# Voltage_Source.net
KiCad netlist of a schematic drawn in Altium Designer
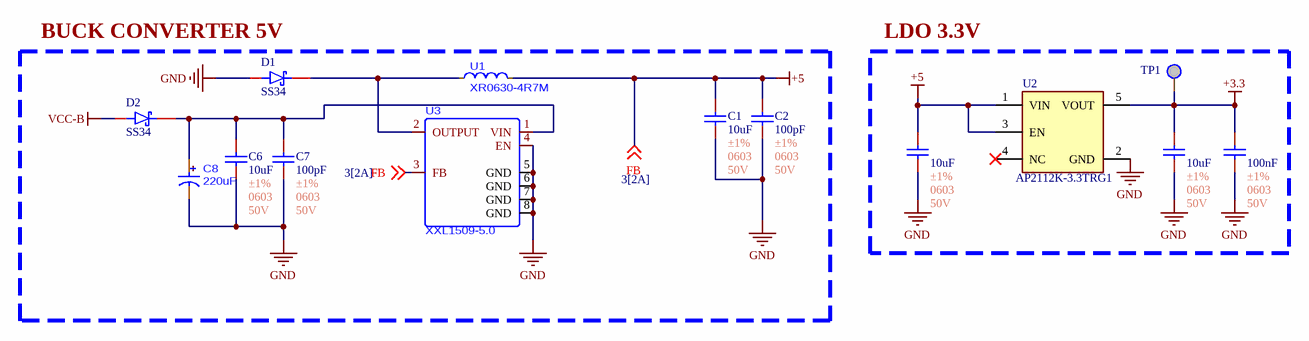
[diagram p0: Voltage Source.SchDoc]

(export (version "E")
  (design (tool "Eeschema 10.0.6"))
  (components
    (comp (ref "C1")
      (value "10uF")
      (footprint "C0603")
      (fields
        (field (name "MANUFACTURER") "YAGEO")
        (field (name "MFR. PART #") "CC0402FRNPO9BN100")
        (field (name "LCSC PART #") "C513681")
        (field (name "TOLERANCE") "±1%")
        (field (name "PACKAGE") "0603")
        (field (name "VOLTAGE RATING") "50V")
      )
      (libsource (lib "Capital") (part "C0603_10uF_±1%"))
    )
    (comp (ref "C2")
      (value "100pF")
      (footprint "C0603")
      (fields
        (field (name "MANUFACTURER") "YAGEO")
        (field (name "MFR. PART #") "CC0402FRNPO9BN100")
        (field (name "LCSC PART #") "C513681")
        (field (name "TOLERANCE") "±1%")
        (field (name "PACKAGE") "0603")
        (field (name "VOLTAGE RATING") "50V")
      )
      (libsource (lib "Capital") (part "C0603_100pF_±1%"))
    )
    (comp (ref "C3")
      (value "10uF")
      (footprint "C0603")
      (description "50V 10pF NP0 ±1% 0402 Multilayer Ceramic Capacitors MLCC - SMD/SMT ROHS")
      (fields
        (field (name "MANUFACTURER") "YAGEO")
        (field (name "MFR. PART #") "CC0402FRNPO9BN100")
        (field (name "TOLERANCE") "±1%")
        (field (name "PACKAGE") "0603")
        (field (name "VOLTAGE RATING") "50V")
      )
      (libsource (lib "") (part "C0603_10uF_±1%_1"))
    )
    (comp (ref "C4")
      (value "10uF")
      (footprint "C0603")
      (description "50V 10pF NP0 ±1% 0402 Multilayer Ceramic Capacitors MLCC - SMD/SMT ROHS")
      (fields
        (field (name "MANUFACTURER") "YAGEO")
        (field (name "MFR. PART #") "CC0402FRNPO9BN100")
        (field (name "TOLERANCE") "±1%")
        (field (name "PACKAGE") "0603")
        (field (name "VOLTAGE RATING") "50V")
      )
      (libsource (lib "") (part "C0603_10uF_±1%_1"))
    )
    (comp (ref "C5")
      (value "100nF")
      (footprint "C0603")
      (description "50V 10pF NP0 ±1% 0402 Multilayer Ceramic Capacitors MLCC - SMD/SMT ROHS")
      (fields
        (field (name "MANUFACTURER") "YAGEO")
        (field (name "MFR. PART #") "CC0402FRNPO9BN100")
        (field (name "TOLERANCE") "±1%")
        (field (name "PACKAGE") "0603")
        (field (name "VOLTAGE RATING") "50V")
      )
      (libsource (lib "Capital") (part "C0603_100nF_±1%"))
    )
    (comp (ref "C6")
      (value "10uF")
      (footprint "C0603")
      (fields
        (field (name "MANUFACTURER") "YAGEO")
        (field (name "MFR. PART #") "CC0402FRNPO9BN100")
        (field (name "LCSC PART #") "C513681")
        (field (name "TOLERANCE") "±1%")
        (field (name "PACKAGE") "0603")
        (field (name "VOLTAGE RATING") "50V")
      )
      (libsource (lib "Capital") (part "C0603_10uF_±1%"))
    )
    (comp (ref "C7")
      (value "100pF")
      (footprint "C0603")
      (fields
        (field (name "MANUFACTURER") "YAGEO")
        (field (name "MFR. PART #") "CC0402FRNPO9BN100")
        (field (name "LCSC PART #") "C513681")
        (field (name "TOLERANCE") "±1%")
        (field (name "PACKAGE") "0603")
        (field (name "VOLTAGE RATING") "50V")
      )
      (libsource (lib "Capital") (part "C0603_100pF_±1%"))
    )
    (comp (ref "C8")
      (value "220uF")
      (footprint "C_220uF_35V_SMD")
      (description "CAP ALUM 220uF ±20% 35V SMD")
      (fields (field (name "MANUFACTURER") "ROQANG") (field (name "MFR. PART #") "RVT1V221M0810"))
      (libsource (lib "Capital") (part "C_220uF_35V_SMD"))
    )
    (comp (ref "D1")
      (value "SS34")
      (footprint "SS34")
      (description "40V Independent 3A 550mV@3A SMA(DO-214AC) Schottky Diodes ROHS")
      (fields
        (field (name "MANUFACTURER") "MDD(Microdiode Semiconductor)")
        (field (name "LCSC PART #") "C8678")
      )
      (libsource (lib "Diode") (part "SS34"))
    )
    (comp (ref "D2")
      (value "SS34")
      (footprint "SS34")
      (description "40V Independent 3A 550mV@3A SMA(DO-214AC) Schottky Diodes ROHS")
      (fields
        (field (name "MANUFACTURER") "MDD(Microdiode Semiconductor)")
        (field (name "LCSC PART #") "C8678")
      )
      (libsource (lib "Diode") (part "SS34"))
    )
    (comp (ref "TP1") (value "TP") (footprint "TP") (libsource (lib "Other") (part "TP")))
    (comp (ref "U1")
      (value "XR0630-4R7M")
      (footprint "SMD,7x6.6mm")
      (description "FIXED IND 4.7uH 6A 33mΩ SMD,0630")
      (fields (field (name "MANUFACTURER") "XR") (field (name "LCSC PART #") "C5307631"))
      (libsource (lib "Inductor") (part "FIXED IND 4.7uH 6A 33mΩ SMD,0630"))
    )
    (comp (ref "U2")
      (value "AP2112K-3.3TRG1")
      (footprint "SOT23-5")
      (description "Linear Voltage Regulator IC Positive Fixed 1 Output 600mA SOT23-5")
      (fields (field (name "MF") "Diodes Inc."))
      (libsource (lib "My Library") (part "AP2112K-3.3TRG1"))
    )
    (comp (ref "U3")
      (value "XXL1509-5.0")
      (footprint "XXL1509-5.0")
      (description "150KHz 3A PWM Buck DC/DC Converter")
      (fields (field (name "MANUFACTURER") "UMW") (field (name "LCSC PART #") "C42376977"))
      (libsource (lib "IC") (part "XXL1509-5.0"))
    )
  )
  (nets
    (net (code "1") (name "+3.3") (class "Default")
      (node (ref "C4") (pin "1") (pinfunction "1_1") (pintype "passive"))
      (node (ref "C5") (pin "1") (pinfunction "1_1") (pintype "passive"))
      (node (ref "TP1") (pin "1") (pinfunction "1_1") (pintype "passive"))
      (node (ref "U2") (pin "5") (pinfunction "VOUT_5") (pintype "power_in"))
    )
    (net (code "2") (name "+5") (class "Default")
      (node (ref "C1") (pin "1") (pinfunction "1_1") (pintype "passive"))
      (node (ref "C2") (pin "1") (pinfunction "1_1") (pintype "passive"))
      (node (ref "C3") (pin "1") (pinfunction "1_1") (pintype "passive"))
      (node (ref "U1") (pin "2") (pinfunction "F_2") (pintype "passive"))
      (node (ref "U2") (pin "1") (pinfunction "VIN_1") (pintype "power_in"))
      (node (ref "U2") (pin "3") (pinfunction "EN_3") (pintype "passive"))
      (node (ref "U3") (pin "3") (pinfunction "FB_3") (pintype "passive"))
    )
    (net (code "3") (name "GND") (class "Default")
      (node (ref "C1") (pin "2") (pinfunction "2_2") (pintype "passive"))
      (node (ref "C2") (pin "2") (pinfunction "2_2") (pintype "passive"))
      (node (ref "C3") (pin "2") (pinfunction "2_2") (pintype "passive"))
      (node (ref "C4") (pin "2") (pinfunction "2_2") (pintype "passive"))
      (node (ref "C5") (pin "2") (pinfunction "2_2") (pintype "passive"))
      (node (ref "C6") (pin "2") (pinfunction "2_2") (pintype "passive"))
      (node (ref "C7") (pin "2") (pinfunction "2_2") (pintype "passive"))
      (node (ref "C8") (pin "2") (pinfunction "2_2") (pintype "passive"))
      (node (ref "D1") (pin "2") (pinfunction "2_2") (pintype "passive"))
      (node (ref "U2") (pin "2") (pinfunction "GND_2") (pintype "power_in"))
      (node (ref "U3") (pin "4") (pinfunction "EN_4") (pintype "passive"))
      (node (ref "U3") (pin "5") (pinfunction "GND_5") (pintype "passive"))
      (node (ref "U3") (pin "6") (pinfunction "GND_6") (pintype "passive"))
      (node (ref "U3") (pin "7") (pinfunction "GND_7") (pintype "passive"))
      (node (ref "U3") (pin "8") (pinfunction "GND_8") (pintype "passive"))
    )
    (net (code "4") (name "Net-(U1-S)") (class "Default")
      (node (ref "D1") (pin "1") (pinfunction "1_1") (pintype "passive"))
      (node (ref "U1") (pin "1") (pinfunction "S_1") (pintype "passive"))
      (node (ref "U3") (pin "2") (pinfunction "OUTPUT_2") (pintype "passive"))
    )
    (net (code "5") (name "Net-(U3-VIN)") (class "Default")
      (node (ref "C6") (pin "1") (pinfunction "1_1") (pintype "passive"))
      (node (ref "C7") (pin "1") (pinfunction "1_1") (pintype "passive"))
      (node (ref "C8") (pin "1") (pinfunction "1_1") (pintype "passive"))
      (node (ref "D2") (pin "1") (pinfunction "1_1") (pintype "passive"))
      (node (ref "U3") (pin "1") (pinfunction "VIN_1") (pintype "passive"))
    )
    (net (code "6") (name "VCC-B") (class "Default")
      (node (ref "D2") (pin "2") (pinfunction "2_2") (pintype "passive"))
    )
    (net (code "7") (name "unconnected-(U2-NC-Pad4)") (class "Default")
      (node (ref "U2") (pin "4") (pinfunction "NC_4") (pintype "passive+no_connect"))
    )
  )
)
